# Inputs.net
KiCad netlist of a schematic drawn in Altium Designer
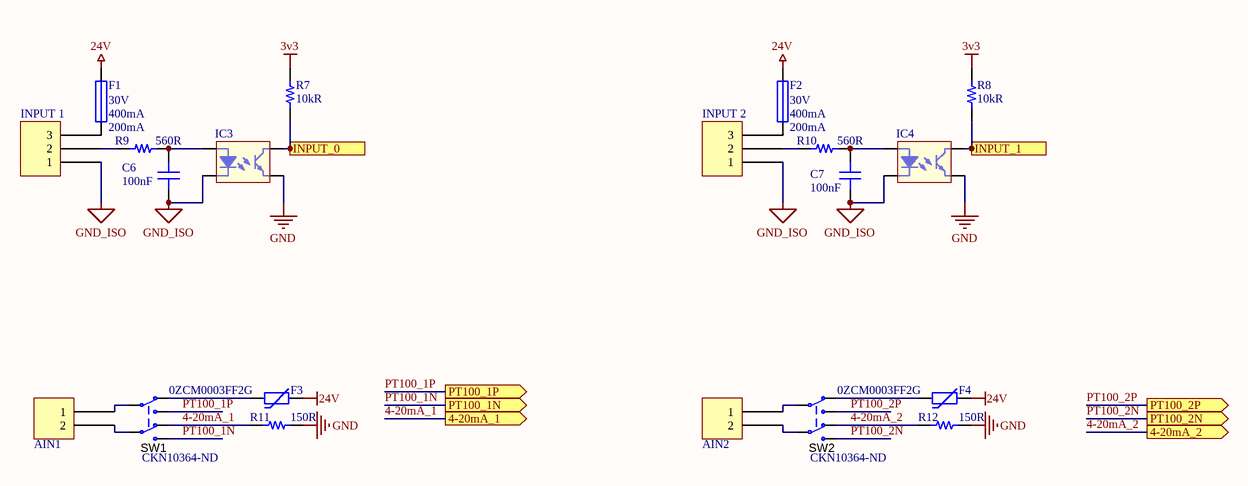
[diagram p0: Inputs.SchDoc]

(export (version "E")
  (design (tool "Eeschema 10.0.6"))
  (components
    (comp (ref "AIN1")
      (value "2 Pin")
      (footprint "TE 282834-2")
      (fields
        (field (name "MANUFACTURER") "TE Connectivity")
        (field (name "MANUFACTURER PART NUMBER") "282834-2")
        (field (name "VOLTAGE") "150V")
      )
      (libsource (lib "yildizIoT Library") (part "2 Pin"))
    )
    (comp (ref "AIN2")
      (value "2 Pin")
      (footprint "TE 282834-2")
      (fields
        (field (name "MANUFACTURER") "TE Connectivity")
        (field (name "MANUFACTURER PART NUMBER") "282834-2")
        (field (name "VOLTAGE") "150V")
      )
      (libsource (lib "yildizIoT Library") (part "2 Pin"))
    )
    (comp (ref "C6")
      (value "100nF")
      (footprint "CAP 0603/1608")
      (description "Ceramic, SMT Capacitor")
      (fields
        (field (name "MANUFACTURER") "Samsung")
        (field (name "MANUFACTURER PART NUMBER") "CL10B104JB8NNNC")
      )
      (libsource (lib "yildizIoT Library") (part "Capacitor - Ceramic"))
    )
    (comp (ref "C7")
      (value "100nF")
      (footprint "CAP 0603/1608")
      (description "Ceramic, SMT Capacitor")
      (fields
        (field (name "MANUFACTURER") "Samsung")
        (field (name "MANUFACTURER PART NUMBER") "CL10B104JB8NNNC")
      )
      (libsource (lib "yildizIoT Library") (part "Capacitor - Ceramic"))
    )
    (comp (ref "F1")
      (value "0ZCJ0020FF2E")
      (footprint "L_1812")
      (description "Fuse")
      (fields
        (field (name "MANUFACTURER") "Bel")
        (field (name "HOLD CURRENT") "200mA")
        (field (name "MAX VOLTAGE RATING (DC)") "30V")
        (field (name "TRIP CURRENT") "400mA")
      )
      (libsource (lib "Muhammet_All_In_One") (part "Fuse 1"))
    )
    (comp (ref "F2")
      (value "0ZCJ0020FF2E")
      (footprint "L_1812")
      (description "Fuse")
      (fields
        (field (name "MANUFACTURER") "Bel")
        (field (name "HOLD CURRENT") "200mA")
        (field (name "MAX VOLTAGE RATING (DC)") "30V")
        (field (name "TRIP CURRENT") "400mA")
      )
      (libsource (lib "Muhammet_All_In_One") (part "Fuse 1"))
    )
    (comp (ref "F3")
      (value "0ZCM0003FF2G")
      (footprint "NTC 0603_1608")
      (description "THERM NTC 0603 (FOR AUTOMOTIVE)")
      (fields (field (name "MANUFACTURER") "Bel"))
      (libsource (lib "Celestial Altium Library - altium_library") (part "Thermistor"))
    )
    (comp (ref "F4")
      (value "0ZCM0003FF2G")
      (footprint "NTC 0603_1608")
      (description "THERM NTC 0603 (FOR AUTOMOTIVE)")
      (fields (field (name "MANUFACTURER") "Bel"))
      (libsource (lib "Celestial Altium Library - altium_library") (part "Thermistor"))
    )
    (comp (ref "IC3")
      (value "EL3H7(B)(TA)-VG")
      (footprint "EL3H7-VG")
      (fields (field (name "MANUFACTURER") "Everlight"))
      (libsource (lib "yildizIoT Library") (part "Optoisolator"))
    )
    (comp (ref "IC4")
      (value "EL3H7(B)(TA)-VG")
      (footprint "EL3H7-VG")
      (fields (field (name "MANUFACTURER") "Everlight"))
      (libsource (lib "yildizIoT Library") (part "Optoisolator"))
    )
    (comp (ref "INPUT 1")
      (value "~")
      (footprint "TE 282834-3")
      (description "TERM BLOCK HDR 3POS R/A 3.81MM")
      (fields
        (field (name "MANUFACTURER") "On-Shore Technology")
        (field (name "MANUFACTURER PART NUMBER") "OSTVN03A150")
      )
      (libsource (lib "yildizIoT Library") (part "3 Pin"))
    )
    (comp (ref "INPUT 2")
      (value "~")
      (footprint "TE 282834-3")
      (description "TERM BLOCK HDR 3POS R/A 3.81MM")
      (fields
        (field (name "MANUFACTURER") "On-Shore Technology")
        (field (name "MANUFACTURER PART NUMBER") "OSTVN03A150")
      )
      (libsource (lib "yildizIoT Library") (part "3 Pin"))
    )
    (comp (ref "R7")
      (value "10kR")
      (footprint "RES 0603/1608")
      (description "Ceramic, SMT Capacitor")
      (fields
        (field (name "MANUFACTURER") "Stackpole Electronics")
        (field (name "MANUFACTURER PART NUMBER") "RNCP0603FTD10K0")
      )
      (libsource (lib "") (part "Resistor_Chip_1"))
    )
    (comp (ref "R8")
      (value "10kR")
      (footprint "RES 0603/1608")
      (description "Ceramic, SMT Capacitor")
      (fields
        (field (name "MANUFACTURER") "Stackpole Electronics")
        (field (name "MANUFACTURER PART NUMBER") "RNCP0603FTD10K0")
      )
      (libsource (lib "") (part "Resistor_Chip_1"))
    )
    (comp (ref "R9")
      (value "560R")
      (footprint "RES 0603/1608")
      (description "Ceramic, SMT Capacitor")
      (fields (field (name "MANUFACTURER") "Rohm") (field (name "MANUFACTURER PART NUMBER") "ESR03EZPJ561"))
      (libsource (lib "yildizIoT Library") (part "Resistor_Chip"))
    )
    (comp (ref "R10")
      (value "560R")
      (footprint "RES 0603/1608")
      (description "Ceramic, SMT Capacitor")
      (fields (field (name "MANUFACTURER") "Rohm") (field (name "MANUFACTURER PART NUMBER") "ESR03EZPJ561"))
      (libsource (lib "yildizIoT Library") (part "Resistor_Chip"))
    )
    (comp (ref "R11")
      (value "150R")
      (footprint "RES 0603/1608")
      (description "Ceramic, SMT Capacitor")
      (fields
        (field (name "MANUFACTURER") "Yageo")
        (field (name "MANUFACTURER PART NUMBER") "RC0603FR-07150RL")
      )
      (libsource (lib "") (part "Resistor_Chip_1"))
    )
    (comp (ref "R12")
      (value "150R")
      (footprint "RES 0603/1608")
      (description "Ceramic, SMT Capacitor")
      (fields
        (field (name "MANUFACTURER") "Yageo")
        (field (name "MANUFACTURER PART NUMBER") "RC0603FR-07150RL")
      )
      (libsource (lib "") (part "Resistor_Chip_1"))
    )
    (comp (ref "SW1")
      (value "SK22D01MG5NS")
      (footprint "SK-22D01-MG 5 NS")
      (description "Switch THD right-angle toggle DPDT")
      (fields (field (name "SUPPLIER PART NUMBER 1") "CKN10364-ND") (field (name "MANUFACTURER") "ITT C&K"))
      (libsource (lib "yildizIoT Library") (part "DPDT Switch"))
    )
    (comp (ref "SW2")
      (value "SK22D01MG5NS")
      (footprint "SK-22D01-MG 5 NS")
      (description "Switch THD right-angle toggle DPDT")
      (fields (field (name "SUPPLIER PART NUMBER 1") "CKN10364-ND") (field (name "MANUFACTURER") "ITT C&K"))
      (libsource (lib "yildizIoT Library") (part "DPDT Switch"))
    )
  )
  (nets
    (net (code "1") (name "/4-20mA_1") (class "Default")
      (node (ref "R11") (pin "1") (pinfunction "1_1") (pintype "passive"))
      (node (ref "SW1") (pin "3") (pinfunction "3_3") (pintype "passive"))
    )
    (net (code "2") (name "/4-20mA_2") (class "Default")
      (node (ref "R12") (pin "1") (pinfunction "1_1") (pintype "passive"))
      (node (ref "SW2") (pin "3") (pinfunction "3_3") (pintype "passive"))
    )
    (net (code "3") (name "/INPUT_0") (class "Default")
      (node (ref "IC3") (pin "4") (pinfunction "4_4") (pintype "passive"))
      (node (ref "R7") (pin "1") (pinfunction "1_1") (pintype "passive"))
    )
    (net (code "4") (name "/INPUT_1") (class "Default")
      (node (ref "IC4") (pin "4") (pinfunction "4_4") (pintype "passive"))
      (node (ref "R8") (pin "1") (pinfunction "1_1") (pintype "passive"))
    )
    (net (code "5") (name "/PT100_1N") (class "Default")
      (node (ref "SW1") (pin "1") (pinfunction "1_1") (pintype "passive"))
    )
    (net (code "6") (name "/PT100_1P") (class "Default")
      (node (ref "SW1") (pin "4") (pinfunction "4_4") (pintype "passive"))
    )
    (net (code "7") (name "/PT100_2N") (class "Default")
      (node (ref "SW2") (pin "1") (pinfunction "1_1") (pintype "passive"))
    )
    (net (code "8") (name "/PT100_2P") (class "Default")
      (node (ref "SW2") (pin "4") (pinfunction "4_4") (pintype "passive"))
    )
    (net (code "9") (name "3v3") (class "Default")
      (node (ref "R7") (pin "2") (pinfunction "2_2") (pintype "passive"))
      (node (ref "R8") (pin "2") (pinfunction "2_2") (pintype "passive"))
    )
    (net (code "10") (name "24V") (class "Default")
      (node (ref "F1") (pin "2") (pinfunction "2_2") (pintype "passive"))
      (node (ref "F2") (pin "2") (pinfunction "2_2") (pintype "passive"))
      (node (ref "F3") (pin "2") (pinfunction "2_2") (pintype "passive"))
      (node (ref "F4") (pin "2") (pinfunction "2_2") (pintype "passive"))
    )
    (net (code "11") (name "GND") (class "Default")
      (node (ref "IC3") (pin "3") (pinfunction "3_3") (pintype "passive"))
      (node (ref "IC4") (pin "3") (pinfunction "3_3") (pintype "passive"))
      (node (ref "R11") (pin "2") (pinfunction "2_2") (pintype "passive"))
      (node (ref "R12") (pin "2") (pinfunction "2_2") (pintype "passive"))
    )
    (net (code "12") (name "GND_ISO") (class "Default")
      (node (ref "C6") (pin "1") (pinfunction "1_1") (pintype "passive"))
      (node (ref "C7") (pin "1") (pinfunction "1_1") (pintype "passive"))
      (node (ref "IC3") (pin "2") (pinfunction "2_2") (pintype "passive"))
      (node (ref "IC4") (pin "2") (pinfunction "2_2") (pintype "passive"))
      (node (ref "INPUT 1") (pin "1") (pinfunction "1_1") (pintype "passive"))
      (node (ref "INPUT 2") (pin "1") (pinfunction "1_1") (pintype "passive"))
    )
    (net (code "13") (name "Net-(AIN1-Pad1)") (class "Default")
      (node (ref "AIN1") (pin "1") (pinfunction "1_1") (pintype "passive"))
      (node (ref "SW1") (pin "5") (pinfunction "5_5") (pintype "passive"))
    )
    (net (code "14") (name "Net-(AIN1-Pad2)") (class "Default")
      (node (ref "AIN1") (pin "2") (pinfunction "2_2") (pintype "passive"))
      (node (ref "SW1") (pin "2") (pinfunction "2_2") (pintype "passive"))
    )
    (net (code "15") (name "Net-(AIN2-Pad1)") (class "Default")
      (node (ref "AIN2") (pin "1") (pinfunction "1_1") (pintype "passive"))
      (node (ref "SW2") (pin "5") (pinfunction "5_5") (pintype "passive"))
    )
    (net (code "16") (name "Net-(AIN2-Pad2)") (class "Default")
      (node (ref "AIN2") (pin "2") (pinfunction "2_2") (pintype "passive"))
      (node (ref "SW2") (pin "2") (pinfunction "2_2") (pintype "passive"))
    )
    (net (code "17") (name "Net-(C6-Pad2)") (class "Default")
      (node (ref "C6") (pin "2") (pinfunction "2_2") (pintype "passive"))
      (node (ref "IC3") (pin "1") (pinfunction "1_1") (pintype "passive"))
      (node (ref "R9") (pin "2") (pinfunction "2_2") (pintype "passive"))
    )
    (net (code "18") (name "Net-(C7-Pad2)") (class "Default")
      (node (ref "C7") (pin "2") (pinfunction "2_2") (pintype "passive"))
      (node (ref "IC4") (pin "1") (pinfunction "1_1") (pintype "passive"))
      (node (ref "R10") (pin "2") (pinfunction "2_2") (pintype "passive"))
    )
    (net (code "19") (name "Net-(F1-Pad1)") (class "Default")
      (node (ref "F1") (pin "1") (pinfunction "1_1") (pintype "passive"))
      (node (ref "INPUT 1") (pin "3") (pinfunction "3_3") (pintype "passive"))
    )
    (net (code "20") (name "Net-(F2-Pad1)") (class "Default")
      (node (ref "F2") (pin "1") (pinfunction "1_1") (pintype "passive"))
      (node (ref "INPUT 2") (pin "3") (pinfunction "3_3") (pintype "passive"))
    )
    (net (code "21") (name "Net-(F3-Pad1)") (class "Default")
      (node (ref "F3") (pin "1") (pinfunction "1_1") (pintype "passive"))
      (node (ref "SW1") (pin "6") (pinfunction "6_6") (pintype "passive"))
    )
    (net (code "22") (name "Net-(F4-Pad1)") (class "Default")
      (node (ref "F4") (pin "1") (pinfunction "1_1") (pintype "passive"))
      (node (ref "SW2") (pin "6") (pinfunction "6_6") (pintype "passive"))
    )
    (net (code "23") (name "Net-(INPUT 1-Pad2)") (class "Default")
      (node (ref "INPUT 1") (pin "2") (pinfunction "2_2") (pintype "passive"))
      (node (ref "R9") (pin "1") (pinfunction "1_1") (pintype "passive"))
    )
    (net (code "24") (name "Net-(INPUT 2-Pad2)") (class "Default")
      (node (ref "INPUT 2") (pin "2") (pinfunction "2_2") (pintype "passive"))
      (node (ref "R10") (pin "1") (pinfunction "1_1") (pintype "passive"))
    )
  )
)
